# BANK34.net
KiCad netlist of a schematic drawn in Altium Designer
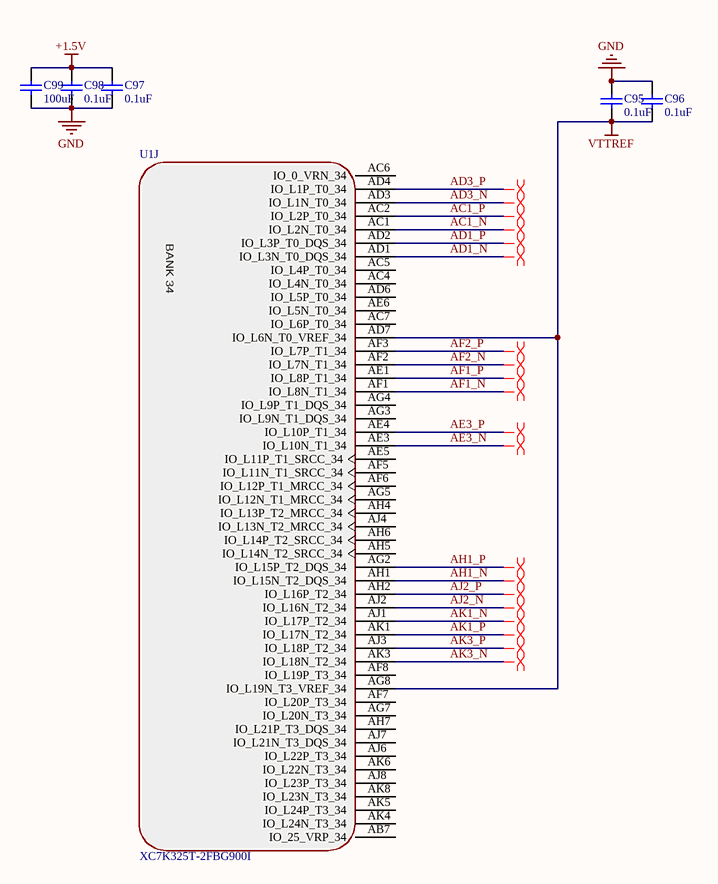
[diagram p0: BANK34.SchDoc]

(export (version "E")
  (design (tool "Eeschema 10.0.6"))
  (components
    (comp (ref "C95")
      (value "0.1uF")
      (footprint "0402")
      (description "Capacitor (Semiconductor SIM Model)")
      (fields (field (name "Comment") "Cap Semi") (field (name "PUBLISHER") "Altium Limited"))
      (libsource (lib "Miscellaneous Devices") (part "Cap Semi"))
    )
    (comp (ref "C96")
      (value "0.1uF")
      (footprint "0402")
      (description "Capacitor (Semiconductor SIM Model)")
      (fields (field (name "Comment") "Cap Semi") (field (name "PUBLISHER") "Altium Limited"))
      (libsource (lib "Miscellaneous Devices") (part "Cap Semi"))
    )
    (comp (ref "C97")
      (value "0.1uF")
      (footprint "0402")
      (description "Capacitor (Semiconductor SIM Model)")
      (fields (field (name "Comment") "Cap Semi") (field (name "PUBLISHER") "Altium Limited"))
      (libsource (lib "Miscellaneous Devices") (part "Cap Semi"))
    )
    (comp (ref "C98")
      (value "0.1uF")
      (footprint "0402")
      (description "Capacitor (Semiconductor SIM Model)")
      (fields (field (name "Comment") "Cap Semi") (field (name "PUBLISHER") "Altium Limited"))
      (libsource (lib "Miscellaneous Devices") (part "Cap Semi"))
    )
    (comp (ref "C99")
      (value "100uF")
      (footprint "0402")
      (description "Capacitor (Semiconductor SIM Model)")
      (fields (field (name "Comment") "Cap Semi") (field (name "PUBLISHER") "Altium Limited"))
      (libsource (lib "Miscellaneous Devices") (part "Cap Semi"))
    )
    (comp (ref "U1") (value "XC7K325T-2FBG900I") (libsource (lib "Schlib1") (part "XC7K325T-2FBG900I")))
  )
  (nets
    (net (code "1") (name "+1.5V") (class "Default")
      (node (ref "C97") (pin "2") (pinfunction "2_2") (pintype "passive"))
      (node (ref "C98") (pin "2") (pinfunction "2_2") (pintype "passive"))
      (node (ref "C99") (pin "2") (pinfunction "2_2") (pintype "passive"))
    )
    (net (code "2") (name "/AC1_N") (class "Default")
      (node (ref "U1") (pin "AC1") (pinfunction "IO_L2N_T0_34_AC1") (pintype "passive"))
    )
    (net (code "3") (name "/AC1_P") (class "Default")
      (node (ref "U1") (pin "AC2") (pinfunction "IO_L2P_T0_34_AC2") (pintype "passive"))
    )
    (net (code "4") (name "/AD1_N") (class "Default")
      (node (ref "U1") (pin "AD1") (pinfunction "IO_L3N_T0_DQS_34_AD1") (pintype "passive"))
    )
    (net (code "5") (name "/AD1_P") (class "Default")
      (node (ref "U1") (pin "AD2") (pinfunction "IO_L3P_T0_DQS_34_AD2") (pintype "passive"))
    )
    (net (code "6") (name "/AD3_N") (class "Default")
      (node (ref "U1") (pin "AD3") (pinfunction "IO_L1N_T0_34_AD3") (pintype "passive"))
    )
    (net (code "7") (name "/AD3_P") (class "Default")
      (node (ref "U1") (pin "AD4") (pinfunction "IO_L1P_T0_34_AD4") (pintype "passive"))
    )
    (net (code "8") (name "/AE3_N") (class "Default")
      (node (ref "U1") (pin "AE3") (pinfunction "IO_L10N_T1_34_AE3") (pintype "passive"))
    )
    (net (code "9") (name "/AE3_P") (class "Default")
      (node (ref "U1") (pin "AE4") (pinfunction "IO_L10P_T1_34_AE4") (pintype "passive"))
    )
    (net (code "10") (name "/AF1_N") (class "Default")
      (node (ref "U1") (pin "AF1") (pinfunction "IO_L8N_T1_34_AF1") (pintype "passive"))
    )
    (net (code "11") (name "/AF1_P") (class "Default")
      (node (ref "U1") (pin "AE1") (pinfunction "IO_L8P_T1_34_AE1") (pintype "passive"))
    )
    (net (code "12") (name "/AF2_N") (class "Default")
      (node (ref "U1") (pin "AF2") (pinfunction "IO_L7N_T1_34_AF2") (pintype "passive"))
    )
    (net (code "13") (name "/AF2_P") (class "Default")
      (node (ref "U1") (pin "AF3") (pinfunction "IO_L7P_T1_34_AF3") (pintype "passive"))
    )
    (net (code "14") (name "/AH1_N") (class "Default")
      (node (ref "U1") (pin "AH1") (pinfunction "IO_L15N_T2_DQS_34_AH1") (pintype "passive"))
    )
    (net (code "15") (name "/AH1_P") (class "Default")
      (node (ref "U1") (pin "AG2") (pinfunction "IO_L15P_T2_DQS_34_AG2") (pintype "passive"))
    )
    (net (code "16") (name "/AJ2_N") (class "Default")
      (node (ref "U1") (pin "AJ2") (pinfunction "IO_L16N_T2_34_AJ2") (pintype "passive"))
    )
    (net (code "17") (name "/AJ2_P") (class "Default")
      (node (ref "U1") (pin "AH2") (pinfunction "IO_L16P_T2_34_AH2") (pintype "passive"))
    )
    (net (code "18") (name "/AK1_N") (class "Default")
      (node (ref "U1") (pin "AJ1") (pinfunction "IO_L17P_T2_34_AJ1") (pintype "passive"))
    )
    (net (code "19") (name "/AK1_P") (class "Default")
      (node (ref "U1") (pin "AK1") (pinfunction "IO_L17N_T2_34_AK1") (pintype "passive"))
    )
    (net (code "20") (name "/AK3_N") (class "Default")
      (node (ref "U1") (pin "AK3") (pinfunction "IO_L18N_T2_34_AK3") (pintype "passive"))
    )
    (net (code "21") (name "/AK3_P") (class "Default")
      (node (ref "U1") (pin "AJ3") (pinfunction "IO_L18P_T2_34_AJ3") (pintype "passive"))
    )
    (net (code "22") (name "GND") (class "Default")
      (node (ref "C95") (pin "2") (pinfunction "2_2") (pintype "passive"))
      (node (ref "C96") (pin "2") (pinfunction "2_2") (pintype "passive"))
      (node (ref "C97") (pin "1") (pinfunction "1_1") (pintype "passive"))
      (node (ref "C98") (pin "1") (pinfunction "1_1") (pintype "passive"))
      (node (ref "C99") (pin "1") (pinfunction "1_1") (pintype "passive"))
    )
    (net (code "23") (name "VTTREF") (class "Default")
      (node (ref "C95") (pin "1") (pinfunction "1_1") (pintype "passive"))
      (node (ref "C96") (pin "1") (pinfunction "1_1") (pintype "passive"))
      (node (ref "U1") (pin "AD7") (pinfunction "IO_L6N_T0_VREF_34_AD7") (pintype "passive"))
      (node (ref "U1") (pin "AG8") (pinfunction "IO_L19N_T3_VREF_34_AG8") (pintype "passive"))
    )
    (net (code "24") (name "unconnected-(U1J-IO_0_VRN_34-PadAC6)") (class "Default")
      (node (ref "U1") (pin "AC6") (pinfunction "IO_0_VRN_34_AC6") (pintype "passive"))
    )
    (net (code "25") (name "unconnected-(U1J-IO_25_VRP_34-PadAB7)") (class "Default")
      (node (ref "U1") (pin "AB7") (pinfunction "IO_25_VRP_34_AB7") (pintype "passive"))
    )
    (net (code "26") (name "unconnected-(U1J-IO_L4N_T0_34-PadAC4)") (class "Default")
      (node (ref "U1") (pin "AC4") (pinfunction "IO_L4N_T0_34_AC4") (pintype "passive"))
    )
    (net (code "27") (name "unconnected-(U1J-IO_L4P_T0_34-PadAC5)") (class "Default")
      (node (ref "U1") (pin "AC5") (pinfunction "IO_L4P_T0_34_AC5") (pintype "passive"))
    )
    (net (code "28") (name "unconnected-(U1J-IO_L5N_T0_34-PadAE6)") (class "Default")
      (node (ref "U1") (pin "AE6") (pinfunction "IO_L5N_T0_34_AE6") (pintype "passive"))
    )
    (net (code "29") (name "unconnected-(U1J-IO_L5P_T0_34-PadAD6)") (class "Default")
      (node (ref "U1") (pin "AD6") (pinfunction "IO_L5P_T0_34_AD6") (pintype "passive"))
    )
    (net (code "30") (name "unconnected-(U1J-IO_L6P_T0_34-PadAC7)") (class "Default")
      (node (ref "U1") (pin "AC7") (pinfunction "IO_L6P_T0_34_AC7") (pintype "passive"))
    )
    (net (code "31") (name "unconnected-(U1J-IO_L9N_T1_DQS_34-PadAG3)") (class "Default")
      (node (ref "U1") (pin "AG3") (pinfunction "IO_L9N_T1_DQS_34_AG3") (pintype "passive"))
    )
    (net (code "32") (name "unconnected-(U1J-IO_L9P_T1_DQS_34-PadAG4)") (class "Default")
      (node (ref "U1") (pin "AG4") (pinfunction "IO_L9P_T1_DQS_34_AG4") (pintype "passive"))
    )
    (net (code "33") (name "unconnected-(U1J-IO_L11N_T1_SRCC_34-PadAF5)") (class "Default")
      (node (ref "U1") (pin "AF5") (pinfunction "IO_L11N_T1_SRCC_34_AF5") (pintype "passive"))
    )
    (net (code "34") (name "unconnected-(U1J-IO_L11P_T1_SRCC_34-PadAE5)") (class "Default")
      (node (ref "U1") (pin "AE5") (pinfunction "IO_L11P_T1_SRCC_34_AE5") (pintype "passive"))
    )
    (net (code "35") (name "unconnected-(U1J-IO_L12N_T1_MRCC_34-PadAG5)") (class "Default")
      (node (ref "U1") (pin "AG5") (pinfunction "IO_L12N_T1_MRCC_34_AG5") (pintype "passive"))
    )
    (net (code "36") (name "unconnected-(U1J-IO_L12P_T1_MRCC_34-PadAF6)") (class "Default")
      (node (ref "U1") (pin "AF6") (pinfunction "IO_L12P_T1_MRCC_34_AF6") (pintype "passive"))
    )
    (net (code "37") (name "unconnected-(U1J-IO_L13N_T2_MRCC_34-PadAJ4)") (class "Default")
      (node (ref "U1") (pin "AJ4") (pinfunction "IO_L13N_T2_MRCC_34_AJ4") (pintype "passive"))
    )
    (net (code "38") (name "unconnected-(U1J-IO_L13P_T2_MRCC_34-PadAH4)") (class "Default")
      (node (ref "U1") (pin "AH4") (pinfunction "IO_L13P_T2_MRCC_34_AH4") (pintype "passive"))
    )
    (net (code "39") (name "unconnected-(U1J-IO_L14N_T2_SRCC_34-PadAH5)") (class "Default")
      (node (ref "U1") (pin "AH5") (pinfunction "IO_L14N_T2_SRCC_34_AH5") (pintype "passive"))
    )
    (net (code "40") (name "unconnected-(U1J-IO_L14P_T2_SRCC_34-PadAH6)") (class "Default")
      (node (ref "U1") (pin "AH6") (pinfunction "IO_L14P_T2_SRCC_34_AH6") (pintype "passive"))
    )
    (net (code "41") (name "unconnected-(U1J-IO_L19P_T3_34-PadAF8)") (class "Default")
      (node (ref "U1") (pin "AF8") (pinfunction "IO_L19P_T3_34_AF8") (pintype "passive"))
    )
    (net (code "42") (name "unconnected-(U1J-IO_L20N_T3_34-PadAG7)") (class "Default")
      (node (ref "U1") (pin "AG7") (pinfunction "IO_L20N_T3_34_AG7") (pintype "passive"))
    )
    (net (code "43") (name "unconnected-(U1J-IO_L20P_T3_34-PadAF7)") (class "Default")
      (node (ref "U1") (pin "AF7") (pinfunction "IO_L20P_T3_34_AF7") (pintype "passive"))
    )
    (net (code "44") (name "unconnected-(U1J-IO_L21N_T3_DQS_34-PadAJ7)") (class "Default")
      (node (ref "U1") (pin "AJ7") (pinfunction "IO_L21N_T3_DQS_34_AJ7") (pintype "passive"))
    )
    (net (code "45") (name "unconnected-(U1J-IO_L21P_T3_DQS_34-PadAH7)") (class "Default")
      (node (ref "U1") (pin "AH7") (pinfunction "IO_L21P_T3_DQS_34_AH7") (pintype "passive"))
    )
    (net (code "46") (name "unconnected-(U1J-IO_L22N_T3_34-PadAK6)") (class "Default")
      (node (ref "U1") (pin "AK6") (pinfunction "IO_L22N_T3_34_AK6") (pintype "passive"))
    )
    (net (code "47") (name "unconnected-(U1J-IO_L22P_T3_34-PadAJ6)") (class "Default")
      (node (ref "U1") (pin "AJ6") (pinfunction "IO_L22P_T3_34_AJ6") (pintype "passive"))
    )
    (net (code "48") (name "unconnected-(U1J-IO_L23N_T3_34-PadAK8)") (class "Default")
      (node (ref "U1") (pin "AK8") (pinfunction "IO_L23N_T3_34_AK8") (pintype "passive"))
    )
    (net (code "49") (name "unconnected-(U1J-IO_L23P_T3_34-PadAJ8)") (class "Default")
      (node (ref "U1") (pin "AJ8") (pinfunction "IO_L23P_T3_34_AJ8") (pintype "passive"))
    )
    (net (code "50") (name "unconnected-(U1J-IO_L24N_T3_34-PadAK4)") (class "Default")
      (node (ref "U1") (pin "AK4") (pinfunction "IO_L24N_T3_34_AK4") (pintype "passive"))
    )
    (net (code "51") (name "unconnected-(U1J-IO_L24P_T3_34-PadAK5)") (class "Default")
      (node (ref "U1") (pin "AK5") (pinfunction "IO_L24P_T3_34_AK5") (pintype "passive"))
    )
  )
)
